# karmanDB_camera.net
KiCad netlist of a schematic drawn in Altium Designer
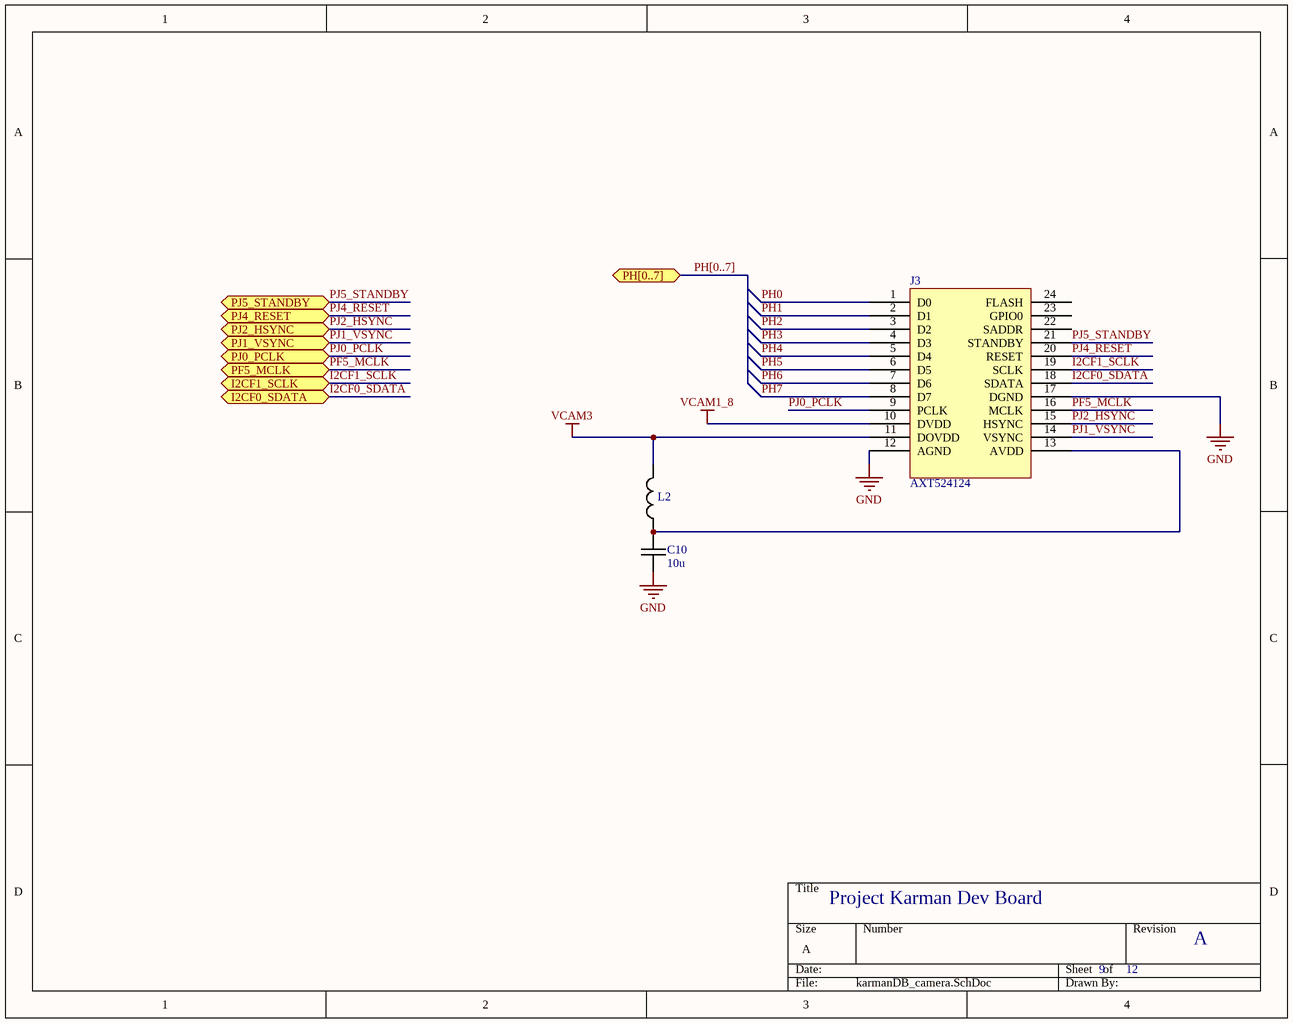
[diagram p0: karmanDB_camera.SchDoc]

(export (version "E")
  (design (tool "Eeschema 10.0.6"))
  (components
    (comp (ref "C10")
      (value "10u")
      (footprint "MURATA_GRM_0603")
      (description "CAP CER 10UF 6.3V 20% X5R 0603")
      (fields
        (field (name "MANUFACTURER") "Murata Electronics North America")
        (field (name "MANUFACTURER PART NUMBER") "GRM188R60J106ME47J")
      )
      (libsource (lib "project_symbols") (part "CAP_MURATA_GRM188R60J106"))
    )
    (comp (ref "J3")
      (value "AXT524124")
      (footprint "AXT524124")
      (description "CONN SOCKET F4S .4MM 24POS SMD")
      (fields (field (name "MANUFACTURER") "Panasonic Electric Works"))
      (libsource (lib "karman_pcb") (part "AXT524124"))
    )
    (comp (ref "L2")
      (value "BLM15BB221SN1D")
      (footprint "BLM15")
      (description "FERRITE CHIP 220 OHM 200MA 0402")
      (fields (field (name "MANUFACTURER") "Murata Electronics North America"))
      (libsource (lib "karman_pcb") (part "BLM15BB221SN1D"))
    )
  )
  (nets
    (net (code "1") (name "/I2CF0_SDATA") (class "Default")
      (node (ref "J3") (pin "18") (pinfunction "SDATA_18") (pintype "passive"))
    )
    (net (code "2") (name "/I2CF1_SCLK") (class "Default")
      (node (ref "J3") (pin "19") (pinfunction "SCLK_19") (pintype "passive"))
    )
    (net (code "3") (name "/PF5_MCLK") (class "Default")
      (node (ref "J3") (pin "16") (pinfunction "MCLK_16") (pintype "passive"))
    )
    (net (code "4") (name "/PH0") (class "Default")
      (node (ref "J3") (pin "1") (pinfunction "D0_1") (pintype "passive"))
    )
    (net (code "5") (name "/PH1") (class "Default")
      (node (ref "J3") (pin "2") (pinfunction "D1_2") (pintype "passive"))
    )
    (net (code "6") (name "/PH2") (class "Default")
      (node (ref "J3") (pin "3") (pinfunction "D2_3") (pintype "passive"))
    )
    (net (code "7") (name "/PH3") (class "Default")
      (node (ref "J3") (pin "4") (pinfunction "D3_4") (pintype "passive"))
    )
    (net (code "8") (name "/PH4") (class "Default")
      (node (ref "J3") (pin "5") (pinfunction "D4_5") (pintype "passive"))
    )
    (net (code "9") (name "/PH5") (class "Default")
      (node (ref "J3") (pin "6") (pinfunction "D5_6") (pintype "passive"))
    )
    (net (code "10") (name "/PH6") (class "Default")
      (node (ref "J3") (pin "7") (pinfunction "D6_7") (pintype "passive"))
    )
    (net (code "11") (name "/PH7") (class "Default")
      (node (ref "J3") (pin "8") (pinfunction "D7_8") (pintype "passive"))
    )
    (net (code "13") (name "/PJ0_PCLK") (class "Default")
      (node (ref "J3") (pin "9") (pinfunction "PCLK_9") (pintype "passive"))
    )
    (net (code "14") (name "/PJ1_VSYNC") (class "Default")
      (node (ref "J3") (pin "14") (pinfunction "VSYNC_14") (pintype "passive"))
    )
    (net (code "15") (name "/PJ2_HSYNC") (class "Default")
      (node (ref "J3") (pin "15") (pinfunction "HSYNC_15") (pintype "passive"))
    )
    (net (code "16") (name "/PJ4_RESET") (class "Default")
      (node (ref "J3") (pin "20") (pinfunction "RESET_20") (pintype "passive"))
    )
    (net (code "17") (name "/PJ5_STANDBY") (class "Default")
      (node (ref "J3") (pin "21") (pinfunction "STANDBY_21") (pintype "passive"))
    )
    (net (code "18") (name "GND") (class "Default")
      (node (ref "C10") (pin "2") (pintype "passive"))
      (node (ref "J3") (pin "12") (pinfunction "AGND_12") (pintype "passive"))
      (node (ref "J3") (pin "17") (pinfunction "DGND_17") (pintype "passive"))
    )
    (net (code "19") (name "Net-(J3-AVDD)") (class "Default")
      (node (ref "C10") (pin "1") (pintype "passive"))
      (node (ref "J3") (pin "13") (pinfunction "AVDD_13") (pintype "passive"))
      (node (ref "L2") (pin "1") (pinfunction "1_1") (pintype "passive"))
    )
    (net (code "20") (name "VCAM1_8") (class "Default")
      (node (ref "J3") (pin "10") (pinfunction "DVDD_10") (pintype "passive"))
    )
    (net (code "21") (name "VCAM3") (class "Default")
      (node (ref "J3") (pin "11") (pinfunction "DOVDD_11") (pintype "passive"))
      (node (ref "L2") (pin "2") (pinfunction "2_2") (pintype "passive"))
    )
    (net (code "22") (name "unconnected-(J3-FLASH-Pad24)") (class "Default")
      (node (ref "J3") (pin "24") (pinfunction "FLASH_24") (pintype "passive"))
    )
    (net (code "23") (name "unconnected-(J3-GPIO0-Pad23)") (class "Default")
      (node (ref "J3") (pin "23") (pinfunction "GPIO0_23") (pintype "passive"))
    )
    (net (code "24") (name "unconnected-(J3-SADDR-Pad22)") (class "Default")
      (node (ref "J3") (pin "22") (pinfunction "SADDR_22") (pintype "passive"))
    )
  )
)
